# CAN.net
KiCad netlist of a schematic drawn in Altium Designer
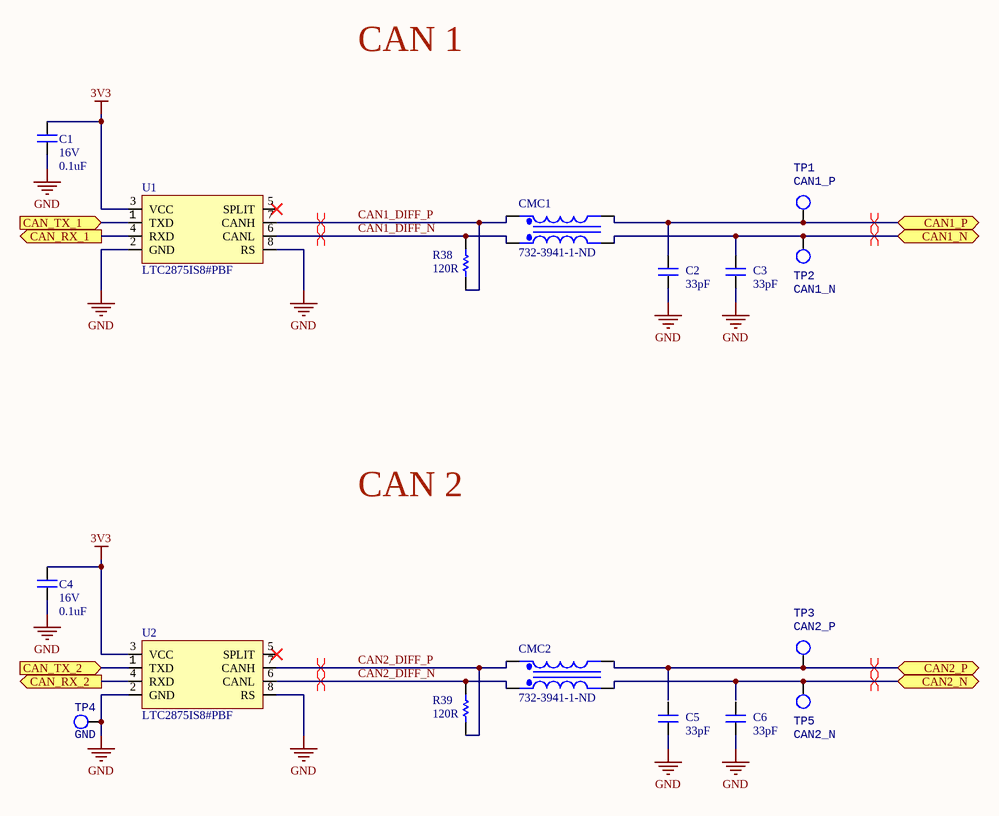
[diagram p0: CAN.SchDoc]

(export (version "E")
  (design (tool "Eeschema 10.0.6"))
  (components
    (comp (ref "C1")
      (value "0.1uF")
      (footprint "CAPC0603(1608)55_N")
      (description "CAP CER 0.1UF 16V X7R 0603")
      (fields (field (name "VOLTAGE RATING") "16V") (field (name "Comment") "CAP_0.1uF_16V_0603"))
      (libsource (lib "UWRT_Schematic_Library_2020") (part "CAP_0.1uF_16V_0603"))
    )
    (comp (ref "C2")
      (value "CAP_33pF_50V_0603")
      (footprint "CAPC0603(1608)55_N")
      (description "CAP CER 33PF 50V C0G/NP0")
      (fields
        (field (name "VOLTAGE") "50V")
        (field (name "TOLERANCE") "5%")
        (field (name "CAPACITANCE") "33pF")
      )
      (libsource (lib "UWRT_Schematic_Library_2020") (part "CAP_33pF_50V_0603"))
    )
    (comp (ref "C3")
      (value "CAP_33pF_50V_0603")
      (footprint "CAPC0603(1608)55_N")
      (description "CAP CER 33PF 50V C0G/NP0")
      (fields
        (field (name "VOLTAGE") "50V")
        (field (name "TOLERANCE") "5%")
        (field (name "CAPACITANCE") "33pF")
      )
      (libsource (lib "UWRT_Schematic_Library_2020") (part "CAP_33pF_50V_0603"))
    )
    (comp (ref "C4")
      (value "0.1uF")
      (footprint "CAPC0603(1608)55_N")
      (description "CAP CER 0.1UF 16V X7R 0603")
      (fields (field (name "VOLTAGE RATING") "16V") (field (name "Comment") "CAP_0.1uF_16V_0603"))
      (libsource (lib "UWRT_Schematic_Library_2020") (part "CAP_0.1uF_16V_0603"))
    )
    (comp (ref "C5")
      (value "CAP_33pF_50V_0603")
      (footprint "CAPC0603(1608)55_N")
      (description "CAP CER 33PF 50V C0G/NP0")
      (fields
        (field (name "VOLTAGE") "50V")
        (field (name "TOLERANCE") "5%")
        (field (name "CAPACITANCE") "33pF")
      )
      (libsource (lib "UWRT_Schematic_Library_2020") (part "CAP_33pF_50V_0603"))
    )
    (comp (ref "C6")
      (value "CAP_33pF_50V_0603")
      (footprint "CAPC0603(1608)55_N")
      (description "CAP CER 33PF 50V C0G/NP0")
      (fields
        (field (name "VOLTAGE") "50V")
        (field (name "TOLERANCE") "5%")
        (field (name "CAPACITANCE") "33pF")
      )
      (libsource (lib "UWRT_Schematic_Library_2020") (part "CAP_33pF_50V_0603"))
    )
    (comp (ref "CMC1")
      (value "CMC_51uH")
      (footprint "744212510")
      (description "CMC 51uH 300MA 2LN SMD")
      (fields (field (name "TOLERANCE") "50%") (field (name "SUPPLIER PART NUMBER 1") "732-3941-1-ND"))
      (libsource (lib "UWRT_Schematic_Library_2020") (part "CMC_51uH"))
    )
    (comp (ref "CMC2")
      (value "CMC_51uH")
      (footprint "744212510")
      (description "CMC 51uH 300MA 2LN SMD")
      (fields (field (name "TOLERANCE") "50%") (field (name "SUPPLIER PART NUMBER 1") "732-3941-1-ND"))
      (libsource (lib "UWRT_Schematic_Library_2020") (part "CMC_51uH"))
    )
    (comp (ref "R38")
      (value "120R")
      (footprint "RESC0603(1608)_N")
      (description "RES SMD 120 OHM 5% 1/10W 0603")
      (fields (field (name "MANUFACTURER") "Yageo") (field (name "MPN") "RC0603JR-07120RL"))
      (libsource (lib "UWRT_Schematic_Library_2020") (part "RES_120R_0603"))
    )
    (comp (ref "R39")
      (value "120R")
      (footprint "RESC0603(1608)_N")
      (description "RES SMD 120 OHM 5% 1/10W 0603")
      (fields (field (name "MANUFACTURER") "Yageo") (field (name "MPN") "RC0603JR-07120RL"))
      (libsource (lib "UWRT_Schematic_Library_2020") (part "RES_120R_0603"))
    )
    (comp (ref "TP1")
      (value "CAN1_P")
      (footprint "TESTPOINT_LOOP")
      (description "Loop testpoint through-hole pad")
      (libsource (lib "UWRT_Schematic_Library_2020") (part "TESTPOINT_LOOP"))
    )
    (comp (ref "TP2")
      (value "CAN1_N")
      (footprint "TESTPOINT_LOOP")
      (description "Loop testpoint through-hole pad")
      (libsource (lib "UWRT_Schematic_Library_2020") (part "TESTPOINT_LOOP"))
    )
    (comp (ref "TP3")
      (value "CAN2_P")
      (footprint "TESTPOINT_LOOP")
      (description "Loop testpoint through-hole pad")
      (libsource (lib "UWRT_Schematic_Library_2020") (part "TESTPOINT_LOOP"))
    )
    (comp (ref "TP4")
      (value "GND")
      (footprint "TESTPOINT_LOOP")
      (description "Loop testpoint through-hole pad")
      (libsource (lib "UWRT_Schematic_Library_2020") (part "TESTPOINT_LOOP"))
    )
    (comp (ref "TP5")
      (value "CAN2_N")
      (footprint "TESTPOINT_LOOP")
      (description "Loop testpoint through-hole pad")
      (libsource (lib "UWRT_Schematic_Library_2020") (part "TESTPOINT_LOOP"))
    )
    (comp (ref "U1")
      (value "IC TXRX CAN")
      (footprint "LT-S8_N")
      (description "IC TXRX CAN 4MBPS 8SO")
      (fields (field (name "MANUFACTURER PART NUMBER 1") "LTC2875IS8#PBF"))
      (libsource (lib "UWRT_Schematic_Library_2020") (part "LTC2875"))
    )
    (comp (ref "U2")
      (value "IC TXRX CAN")
      (footprint "LT-S8_N")
      (description "IC TXRX CAN 4MBPS 8SO")
      (fields (field (name "MANUFACTURER PART NUMBER 1") "LTC2875IS8#PBF"))
      (libsource (lib "UWRT_Schematic_Library_2020") (part "LTC2875"))
    )
  )
  (nets
    (net (code "1") (name "/CAN1_DIFF_N") (class "Default")
      (node (ref "CMC1") (pin "1") (pinfunction "Pri+_1") (pintype "passive"))
      (node (ref "R38") (pin "1") (pinfunction "1_1") (pintype "passive"))
      (node (ref "U1") (pin "6") (pinfunction "CANL_6") (pintype "passive"))
    )
    (net (code "2") (name "/CAN1_DIFF_P") (class "Default")
      (node (ref "CMC1") (pin "3") (pinfunction "Sec+_3") (pintype "passive"))
      (node (ref "R38") (pin "2") (pinfunction "2_2") (pintype "passive"))
      (node (ref "U1") (pin "7") (pinfunction "CANH_7") (pintype "passive"))
    )
    (net (code "3") (name "/CAN1_N") (class "Default")
      (node (ref "C3") (pin "2") (pinfunction "2_2") (pintype "passive"))
      (node (ref "CMC1") (pin "5") (pinfunction "Pri-_5") (pintype "passive"))
      (node (ref "TP2") (pin "1") (pintype "passive"))
    )
    (net (code "4") (name "/CAN1_P") (class "Default")
      (node (ref "C2") (pin "2") (pinfunction "2_2") (pintype "passive"))
      (node (ref "CMC1") (pin "4") (pinfunction "Sec-_4") (pintype "passive"))
      (node (ref "TP1") (pin "1") (pintype "passive"))
    )
    (net (code "5") (name "/CAN2_DIFF_N") (class "Default")
      (node (ref "CMC2") (pin "1") (pinfunction "Pri+_1") (pintype "passive"))
      (node (ref "R39") (pin "1") (pinfunction "1_1") (pintype "passive"))
      (node (ref "U2") (pin "6") (pinfunction "CANL_6") (pintype "passive"))
    )
    (net (code "6") (name "/CAN2_DIFF_P") (class "Default")
      (node (ref "CMC2") (pin "3") (pinfunction "Sec+_3") (pintype "passive"))
      (node (ref "R39") (pin "2") (pinfunction "2_2") (pintype "passive"))
      (node (ref "U2") (pin "7") (pinfunction "CANH_7") (pintype "passive"))
    )
    (net (code "7") (name "/CAN2_N") (class "Default")
      (node (ref "CMC2") (pin "5") (pinfunction "Pri-_5") (pintype "passive"))
      (node (ref "TP5") (pin "1") (pintype "passive"))
    )
    (net (code "8") (name "/CAN2_P") (class "Default")
      (node (ref "CMC2") (pin "4") (pinfunction "Sec-_4") (pintype "passive"))
      (node (ref "TP3") (pin "1") (pintype "passive"))
    )
    (net (code "9") (name "/CAN_RX_1") (class "Default")
      (node (ref "U1") (pin "4") (pinfunction "RXD_4") (pintype "passive"))
    )
    (net (code "10") (name "/CAN_RX_2") (class "Default")
      (node (ref "U2") (pin "4") (pinfunction "RXD_4") (pintype "passive"))
    )
    (net (code "11") (name "/CAN_TX_1") (class "Default")
      (node (ref "U1") (pin "1") (pinfunction "TXD_1") (pintype "passive"))
    )
    (net (code "12") (name "/CAN_TX_2") (class "Default")
      (node (ref "U2") (pin "1") (pinfunction "TXD_1") (pintype "passive"))
    )
    (net (code "13") (name "3V3") (class "Default")
      (node (ref "C1") (pin "1") (pinfunction "1_1") (pintype "passive"))
      (node (ref "C4") (pin "1") (pinfunction "1_1") (pintype "passive"))
      (node (ref "U1") (pin "3") (pinfunction "VCC_3") (pintype "passive"))
      (node (ref "U2") (pin "3") (pinfunction "VCC_3") (pintype "passive"))
    )
    (net (code "14") (name "GND") (class "Default")
      (node (ref "C1") (pin "2") (pinfunction "2_2") (pintype "passive"))
      (node (ref "C2") (pin "1") (pinfunction "1_1") (pintype "passive"))
      (node (ref "C3") (pin "1") (pinfunction "1_1") (pintype "passive"))
      (node (ref "C4") (pin "2") (pinfunction "2_2") (pintype "passive"))
      (node (ref "C5") (pin "1") (pinfunction "1_1") (pintype "passive"))
      (node (ref "C6") (pin "1") (pinfunction "1_1") (pintype "passive"))
      (node (ref "TP4") (pin "1") (pintype "passive"))
      (node (ref "U1") (pin "2") (pinfunction "GND_2") (pintype "passive"))
      (node (ref "U1") (pin "8") (pinfunction "RS_8") (pintype "passive"))
      (node (ref "U2") (pin "2") (pinfunction "GND_2") (pintype "passive"))
      (node (ref "U2") (pin "8") (pinfunction "RS_8") (pintype "passive"))
    )
    (net (code "15") (name "unconnected-(C5-Pad2)") (class "Default")
      (node (ref "C5") (pin "2") (pinfunction "2_2") (pintype "passive"))
    )
    (net (code "16") (name "unconnected-(C6-Pad2)") (class "Default")
      (node (ref "C6") (pin "2") (pinfunction "2_2") (pintype "passive"))
    )
    (net (code "17") (name "unconnected-(U1-SPLIT-Pad5)") (class "Default")
      (node (ref "U1") (pin "5") (pinfunction "SPLIT_5") (pintype "passive+no_connect"))
    )
    (net (code "18") (name "unconnected-(U2-SPLIT-Pad5)") (class "Default")
      (node (ref "U2") (pin "5") (pinfunction "SPLIT_5") (pintype "passive+no_connect"))
    )
  )
)
